# ads1115.net
KiCad netlist of a schematic drawn in EAGLE
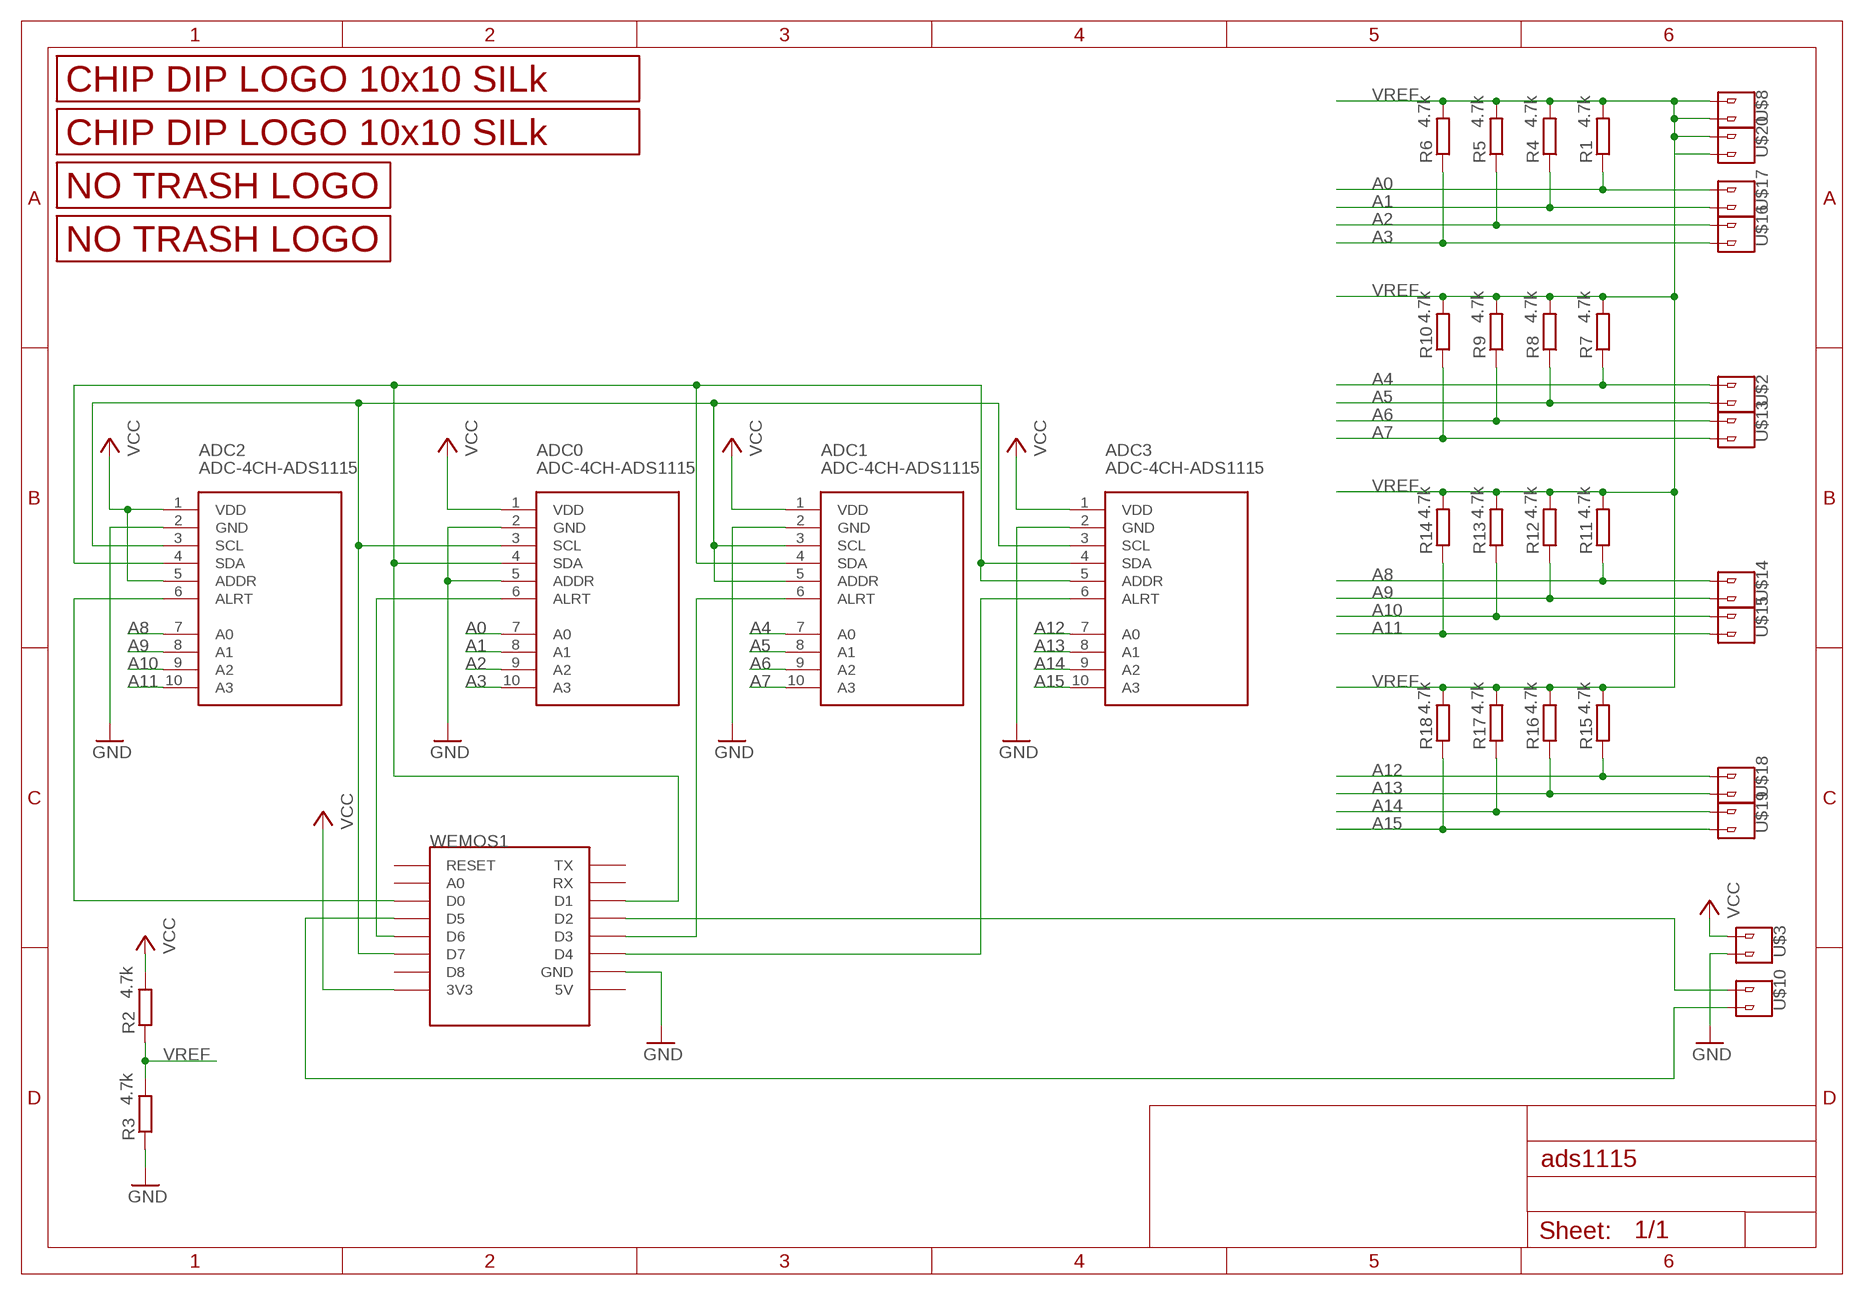
[diagram p0: schematic, sheet 1]

(export (version "E")
  (design (tool "Eeschema 10.0.6"))
  (components
    (comp (ref "ADC0")
      (value "ADC-4CH-ADS1115")
      (footprint "eagle-import:ADC-4CH-ADS1115_NO")
      (libsource (lib "eagle-import") (part "ADC-4CH-ADS1115"))
    )
    (comp (ref "ADC1")
      (value "ADC-4CH-ADS1115")
      (footprint "eagle-import:ADC-4CH-ADS1115_NO")
      (libsource (lib "eagle-import") (part "ADC-4CH-ADS1115"))
    )
    (comp (ref "ADC2")
      (value "ADC-4CH-ADS1115")
      (footprint "eagle-import:ADC-4CH-ADS1115_NO")
      (libsource (lib "eagle-import") (part "ADC-4CH-ADS1115"))
    )
    (comp (ref "ADC3")
      (value "ADC-4CH-ADS1115")
      (footprint "eagle-import:ADC-4CH-ADS1115_NO")
      (libsource (lib "eagle-import") (part "ADC-4CH-ADS1115"))
    )
    (comp (ref "R1")
      (value "4.7k")
      (footprint "eagle-import:M0805")
      (libsource (lib "eagle-import") (part "R-EU_M0805"))
    )
    (comp (ref "R2")
      (value "4.7k")
      (footprint "eagle-import:M0805")
      (libsource (lib "eagle-import") (part "R-EU_M0805"))
    )
    (comp (ref "R3")
      (value "4.7k")
      (footprint "eagle-import:M0805")
      (libsource (lib "eagle-import") (part "R-EU_M0805"))
    )
    (comp (ref "R4")
      (value "4.7k")
      (footprint "eagle-import:M0805")
      (libsource (lib "eagle-import") (part "R-EU_M0805"))
    )
    (comp (ref "R5")
      (value "4.7k")
      (footprint "eagle-import:M0805")
      (libsource (lib "eagle-import") (part "R-EU_M0805"))
    )
    (comp (ref "R6")
      (value "4.7k")
      (footprint "eagle-import:M0805")
      (libsource (lib "eagle-import") (part "R-EU_M0805"))
    )
    (comp (ref "R7")
      (value "4.7k")
      (footprint "eagle-import:M0805")
      (libsource (lib "eagle-import") (part "R-EU_M0805"))
    )
    (comp (ref "R8")
      (value "4.7k")
      (footprint "eagle-import:M0805")
      (libsource (lib "eagle-import") (part "R-EU_M0805"))
    )
    (comp (ref "R9")
      (value "4.7k")
      (footprint "eagle-import:M0805")
      (libsource (lib "eagle-import") (part "R-EU_M0805"))
    )
    (comp (ref "R10")
      (value "4.7k")
      (footprint "eagle-import:M0805")
      (libsource (lib "eagle-import") (part "R-EU_M0805"))
    )
    (comp (ref "R11")
      (value "4.7k")
      (footprint "eagle-import:M0805")
      (libsource (lib "eagle-import") (part "R-EU_M0805"))
    )
    (comp (ref "R12")
      (value "4.7k")
      (footprint "eagle-import:M0805")
      (libsource (lib "eagle-import") (part "R-EU_M0805"))
    )
    (comp (ref "R13")
      (value "4.7k")
      (footprint "eagle-import:M0805")
      (libsource (lib "eagle-import") (part "R-EU_M0805"))
    )
    (comp (ref "R14")
      (value "4.7k")
      (footprint "eagle-import:M0805")
      (libsource (lib "eagle-import") (part "R-EU_M0805"))
    )
    (comp (ref "R15")
      (value "4.7k")
      (footprint "eagle-import:M0805")
      (libsource (lib "eagle-import") (part "R-EU_M0805"))
    )
    (comp (ref "R16")
      (value "4.7k")
      (footprint "eagle-import:M0805")
      (libsource (lib "eagle-import") (part "R-EU_M0805"))
    )
    (comp (ref "R17")
      (value "4.7k")
      (footprint "eagle-import:M0805")
      (libsource (lib "eagle-import") (part "R-EU_M0805"))
    )
    (comp (ref "R18")
      (value "4.7k")
      (footprint "eagle-import:M0805")
      (libsource (lib "eagle-import") (part "R-EU_M0805"))
    )
    (comp (ref "U$1")
      (value "LOGO_10X10_SILK")
      (footprint "eagle-import:LOGO2_10X10_SILK")
      (libsource (lib "eagle-import") (part "LOGO_10X10_SILK"))
    )
    (comp (ref "U$2")
      (value "V1")
      (footprint "eagle-import:2_SCREW_PIN")
      (libsource (lib "eagle-import") (part "2_PIN_CONNECTOR"))
    )
    (comp (ref "U$3")
      (value "V1")
      (footprint "eagle-import:2_SCREW_PIN")
      (libsource (lib "eagle-import") (part "2_PIN_CONNECTOR"))
    )
    (comp (ref "U$4")
      (value "LOGO_NO_TRASHNO_TRASH")
      (footprint "eagle-import:LOGO_ROHS_NO_TRASH")
      (libsource (lib "eagle-import") (part "LOGO_NO_TRASHNO_TRASH"))
    )
    (comp (ref "U$8")
      (value "V1")
      (footprint "eagle-import:2_SCREW_PIN")
      (libsource (lib "eagle-import") (part "2_PIN_CONNECTOR"))
    )
    (comp (ref "U$9")
      (value "LOGO_NO_TRASHROHS")
      (footprint "eagle-import:LOGO_ROHS_SYM")
      (libsource (lib "eagle-import") (part "LOGO_NO_TRASHROHS"))
    )
    (comp (ref "U$10")
      (value "V1")
      (footprint "eagle-import:2_SCREW_PIN")
      (libsource (lib "eagle-import") (part "2_PIN_CONNECTOR"))
    )
    (comp (ref "U$11")
      (value "LOGO_10X10_SILK")
      (footprint "eagle-import:LOGO2_10X10_SILK")
      (libsource (lib "eagle-import") (part "LOGO_10X10_SILK"))
    )
    (comp (ref "U$13")
      (value "V1")
      (footprint "eagle-import:2_SCREW_PIN")
      (libsource (lib "eagle-import") (part "2_PIN_CONNECTOR"))
    )
    (comp (ref "U$14")
      (value "V1")
      (footprint "eagle-import:2_SCREW_PIN")
      (libsource (lib "eagle-import") (part "2_PIN_CONNECTOR"))
    )
    (comp (ref "U$15")
      (value "V1")
      (footprint "eagle-import:2_SCREW_PIN")
      (libsource (lib "eagle-import") (part "2_PIN_CONNECTOR"))
    )
    (comp (ref "U$16")
      (value "V1")
      (footprint "eagle-import:2_SCREW_PIN")
      (libsource (lib "eagle-import") (part "2_PIN_CONNECTOR"))
    )
    (comp (ref "U$17")
      (value "V1")
      (footprint "eagle-import:2_SCREW_PIN")
      (libsource (lib "eagle-import") (part "2_PIN_CONNECTOR"))
    )
    (comp (ref "U$18")
      (value "V1")
      (footprint "eagle-import:2_SCREW_PIN")
      (libsource (lib "eagle-import") (part "2_PIN_CONNECTOR"))
    )
    (comp (ref "U$19")
      (value "V1")
      (footprint "eagle-import:2_SCREW_PIN")
      (libsource (lib "eagle-import") (part "2_PIN_CONNECTOR"))
    )
    (comp (ref "U$20")
      (value "V1")
      (footprint "eagle-import:2_SCREW_PIN")
      (libsource (lib "eagle-import") (part "2_PIN_CONNECTOR"))
    )
    (comp (ref "WEMOS1")
      (value "WEMOS-D1-MINITXT")
      (footprint "eagle-import:WEMOS-D1-MINI")
      (libsource (lib "eagle-import") (part "WEMOS-D1-MINITXT"))
    )
  )
  (nets
    (net (code "1") (name "/A0") (class "Default")
      (node (ref "ADC0") (pin "7") (pinfunction "A0_7") (pintype "input"))
      (node (ref "R1") (pin "1") (pinfunction "1_1") (pintype "passive"))
      (node (ref "U$17") (pin "P$1") (pinfunction "1_P$1") (pintype "passive"))
    )
    (net (code "2") (name "/A1") (class "Default")
      (node (ref "ADC0") (pin "8") (pinfunction "A1_8") (pintype "input"))
      (node (ref "R4") (pin "1") (pinfunction "1_1") (pintype "passive"))
      (node (ref "U$17") (pin "P$2") (pinfunction "2_P$2") (pintype "passive"))
    )
    (net (code "3") (name "/A2") (class "Default")
      (node (ref "ADC0") (pin "9") (pinfunction "A2_9") (pintype "input"))
      (node (ref "R5") (pin "1") (pinfunction "1_1") (pintype "passive"))
      (node (ref "U$16") (pin "P$1") (pinfunction "1_P$1") (pintype "passive"))
    )
    (net (code "4") (name "/A3") (class "Default")
      (node (ref "ADC0") (pin "10") (pinfunction "A3_10") (pintype "input"))
      (node (ref "R6") (pin "1") (pinfunction "1_1") (pintype "passive"))
      (node (ref "U$16") (pin "P$2") (pinfunction "2_P$2") (pintype "passive"))
    )
    (net (code "5") (name "/A4") (class "Default")
      (node (ref "ADC1") (pin "7") (pinfunction "A0_7") (pintype "input"))
      (node (ref "R7") (pin "1") (pinfunction "1_1") (pintype "passive"))
      (node (ref "U$2") (pin "P$1") (pinfunction "1_P$1") (pintype "passive"))
    )
    (net (code "6") (name "/A5") (class "Default")
      (node (ref "ADC1") (pin "8") (pinfunction "A1_8") (pintype "input"))
      (node (ref "R8") (pin "1") (pinfunction "1_1") (pintype "passive"))
      (node (ref "U$2") (pin "P$2") (pinfunction "2_P$2") (pintype "passive"))
    )
    (net (code "7") (name "/A6") (class "Default")
      (node (ref "ADC1") (pin "9") (pinfunction "A2_9") (pintype "input"))
      (node (ref "R9") (pin "1") (pinfunction "1_1") (pintype "passive"))
      (node (ref "U$13") (pin "P$1") (pinfunction "1_P$1") (pintype "passive"))
    )
    (net (code "8") (name "/A7") (class "Default")
      (node (ref "ADC1") (pin "10") (pinfunction "A3_10") (pintype "input"))
      (node (ref "R10") (pin "1") (pinfunction "1_1") (pintype "passive"))
      (node (ref "U$13") (pin "P$2") (pinfunction "2_P$2") (pintype "passive"))
    )
    (net (code "9") (name "/A8") (class "Default")
      (node (ref "ADC2") (pin "7") (pinfunction "A0_7") (pintype "input"))
      (node (ref "R11") (pin "1") (pinfunction "1_1") (pintype "passive"))
      (node (ref "U$14") (pin "P$1") (pinfunction "1_P$1") (pintype "passive"))
    )
    (net (code "10") (name "/A9") (class "Default")
      (node (ref "ADC2") (pin "8") (pinfunction "A1_8") (pintype "input"))
      (node (ref "R12") (pin "1") (pinfunction "1_1") (pintype "passive"))
      (node (ref "U$14") (pin "P$2") (pinfunction "2_P$2") (pintype "passive"))
    )
    (net (code "11") (name "/A10") (class "Default")
      (node (ref "ADC2") (pin "9") (pinfunction "A2_9") (pintype "input"))
      (node (ref "R13") (pin "1") (pinfunction "1_1") (pintype "passive"))
      (node (ref "U$15") (pin "P$1") (pinfunction "1_P$1") (pintype "passive"))
    )
    (net (code "12") (name "/A11") (class "Default")
      (node (ref "ADC2") (pin "10") (pinfunction "A3_10") (pintype "input"))
      (node (ref "R14") (pin "1") (pinfunction "1_1") (pintype "passive"))
      (node (ref "U$15") (pin "P$2") (pinfunction "2_P$2") (pintype "passive"))
    )
    (net (code "13") (name "/A12") (class "Default")
      (node (ref "ADC3") (pin "7") (pinfunction "A0_7") (pintype "input"))
      (node (ref "R15") (pin "1") (pinfunction "1_1") (pintype "passive"))
      (node (ref "U$18") (pin "P$1") (pinfunction "1_P$1") (pintype "passive"))
    )
    (net (code "14") (name "/A13") (class "Default")
      (node (ref "ADC3") (pin "8") (pinfunction "A1_8") (pintype "input"))
      (node (ref "R16") (pin "1") (pinfunction "1_1") (pintype "passive"))
      (node (ref "U$18") (pin "P$2") (pinfunction "2_P$2") (pintype "passive"))
    )
    (net (code "15") (name "/A14") (class "Default")
      (node (ref "ADC3") (pin "9") (pinfunction "A2_9") (pintype "input"))
      (node (ref "R17") (pin "1") (pinfunction "1_1") (pintype "passive"))
      (node (ref "U$19") (pin "P$1") (pinfunction "1_P$1") (pintype "passive"))
    )
    (net (code "16") (name "/A15") (class "Default")
      (node (ref "ADC3") (pin "10") (pinfunction "A3_10") (pintype "input"))
      (node (ref "R18") (pin "1") (pinfunction "1_1") (pintype "passive"))
      (node (ref "U$19") (pin "P$2") (pinfunction "2_P$2") (pintype "passive"))
    )
    (net (code "17") (name "/VREF") (class "Default")
      (node (ref "R1") (pin "2") (pinfunction "2_2") (pintype "passive"))
      (node (ref "R10") (pin "2") (pinfunction "2_2") (pintype "passive"))
      (node (ref "R11") (pin "2") (pinfunction "2_2") (pintype "passive"))
      (node (ref "R12") (pin "2") (pinfunction "2_2") (pintype "passive"))
      (node (ref "R13") (pin "2") (pinfunction "2_2") (pintype "passive"))
      (node (ref "R14") (pin "2") (pinfunction "2_2") (pintype "passive"))
      (node (ref "R15") (pin "2") (pinfunction "2_2") (pintype "passive"))
      (node (ref "R16") (pin "2") (pinfunction "2_2") (pintype "passive"))
      (node (ref "R17") (pin "2") (pinfunction "2_2") (pintype "passive"))
      (node (ref "R18") (pin "2") (pinfunction "2_2") (pintype "passive"))
      (node (ref "R2") (pin "1") (pinfunction "1_1") (pintype "passive"))
      (node (ref "R3") (pin "2") (pinfunction "2_2") (pintype "passive"))
      (node (ref "R4") (pin "2") (pinfunction "2_2") (pintype "passive"))
      (node (ref "R5") (pin "2") (pinfunction "2_2") (pintype "passive"))
      (node (ref "R6") (pin "2") (pinfunction "2_2") (pintype "passive"))
      (node (ref "R7") (pin "2") (pinfunction "2_2") (pintype "passive"))
      (node (ref "R8") (pin "2") (pinfunction "2_2") (pintype "passive"))
      (node (ref "R9") (pin "2") (pinfunction "2_2") (pintype "passive"))
      (node (ref "U$20") (pin "P$1") (pinfunction "1_P$1") (pintype "passive"))
      (node (ref "U$20") (pin "P$2") (pinfunction "2_P$2") (pintype "passive"))
      (node (ref "U$8") (pin "P$1") (pinfunction "1_P$1") (pintype "passive"))
      (node (ref "U$8") (pin "P$2") (pinfunction "2_P$2") (pintype "passive"))
    )
    (net (code "18") (name "GND") (class "Default")
      (node (ref "ADC0") (pin "2") (pinfunction "GND_2") (pintype "power_in"))
      (node (ref "ADC0") (pin "5") (pinfunction "ADDR_5") (pintype "bidirectional"))
      (node (ref "ADC1") (pin "2") (pinfunction "GND_2") (pintype "power_in"))
      (node (ref "ADC2") (pin "2") (pinfunction "GND_2") (pintype "power_in"))
      (node (ref "ADC3") (pin "2") (pinfunction "GND_2") (pintype "power_in"))
      (node (ref "R3") (pin "1") (pinfunction "1_1") (pintype "passive"))
      (node (ref "U$3") (pin "P$2") (pinfunction "2_P$2") (pintype "passive"))
      (node (ref "WEMOS1") (pin "GND") (pinfunction "GND_GND") (pintype "bidirectional"))
    )
    (net (code "19") (name "Net-(ADC0-ALRT)") (class "Default")
      (node (ref "ADC0") (pin "6") (pinfunction "ALRT_6") (pintype "bidirectional"))
      (node (ref "WEMOS1") (pin "D6") (pinfunction "D6_D6") (pintype "bidirectional"))
    )
    (net (code "20") (name "Net-(ADC0-SCL)") (class "Default")
      (node (ref "ADC0") (pin "3") (pinfunction "SCL_3") (pintype "bidirectional"))
      (node (ref "ADC1") (pin "3") (pinfunction "SCL_3") (pintype "bidirectional"))
      (node (ref "ADC1") (pin "5") (pinfunction "ADDR_5") (pintype "bidirectional"))
      (node (ref "ADC2") (pin "3") (pinfunction "SCL_3") (pintype "bidirectional"))
      (node (ref "ADC3") (pin "3") (pinfunction "SCL_3") (pintype "bidirectional"))
      (node (ref "WEMOS1") (pin "D7") (pinfunction "D7_D7") (pintype "bidirectional"))
    )
    (net (code "21") (name "Net-(ADC0-SDA)") (class "Default")
      (node (ref "ADC0") (pin "4") (pinfunction "SDA_4") (pintype "bidirectional"))
      (node (ref "ADC1") (pin "4") (pinfunction "SDA_4") (pintype "bidirectional"))
      (node (ref "ADC2") (pin "4") (pinfunction "SDA_4") (pintype "bidirectional"))
      (node (ref "ADC3") (pin "4") (pinfunction "SDA_4") (pintype "bidirectional"))
      (node (ref "ADC3") (pin "5") (pinfunction "ADDR_5") (pintype "bidirectional"))
      (node (ref "WEMOS1") (pin "D1") (pinfunction "D1_D1") (pintype "bidirectional"))
    )
    (net (code "22") (name "Net-(ADC1-ALRT)") (class "Default")
      (node (ref "ADC1") (pin "6") (pinfunction "ALRT_6") (pintype "bidirectional"))
      (node (ref "WEMOS1") (pin "D3") (pinfunction "D3_D3") (pintype "bidirectional"))
    )
    (net (code "23") (name "Net-(ADC2-ALRT)") (class "Default")
      (node (ref "ADC2") (pin "6") (pinfunction "ALRT_6") (pintype "bidirectional"))
      (node (ref "WEMOS1") (pin "D0") (pinfunction "D0_D0") (pintype "bidirectional"))
    )
    (net (code "24") (name "Net-(ADC3-ALRT)") (class "Default")
      (node (ref "ADC3") (pin "6") (pinfunction "ALRT_6") (pintype "bidirectional"))
      (node (ref "WEMOS1") (pin "D4") (pinfunction "D4_D4") (pintype "bidirectional"))
    )
    (net (code "25") (name "Net-(U$10-1)") (class "Default")
      (node (ref "U$10") (pin "P$1") (pinfunction "1_P$1") (pintype "passive"))
      (node (ref "WEMOS1") (pin "D2") (pinfunction "D2_D2") (pintype "bidirectional"))
    )
    (net (code "26") (name "Net-(U$10-2)") (class "Default")
      (node (ref "U$10") (pin "P$2") (pinfunction "2_P$2") (pintype "passive"))
      (node (ref "WEMOS1") (pin "D5") (pinfunction "D5_D5") (pintype "bidirectional"))
    )
    (net (code "27") (name "VCC") (class "Default")
      (node (ref "ADC0") (pin "1") (pinfunction "VDD_1") (pintype "power_in"))
      (node (ref "ADC1") (pin "1") (pinfunction "VDD_1") (pintype "power_in"))
      (node (ref "ADC2") (pin "1") (pinfunction "VDD_1") (pintype "power_in"))
      (node (ref "ADC2") (pin "5") (pinfunction "ADDR_5") (pintype "bidirectional"))
      (node (ref "ADC3") (pin "1") (pinfunction "VDD_1") (pintype "power_in"))
      (node (ref "R2") (pin "2") (pinfunction "2_2") (pintype "passive"))
      (node (ref "U$3") (pin "P$1") (pinfunction "1_P$1") (pintype "passive"))
      (node (ref "WEMOS1") (pin "3V3") (pinfunction "3V3_3V3") (pintype "bidirectional"))
    )
    (net (code "28") (name "unconnected-(WEMOS1-Pad5V)") (class "Default")
      (node (ref "WEMOS1") (pin "5V") (pinfunction "5V_5V") (pintype "bidirectional"))
    )
    (net (code "29") (name "unconnected-(WEMOS1-PadA0)") (class "Default")
      (node (ref "WEMOS1") (pin "A0") (pinfunction "A0_A0") (pintype "bidirectional"))
    )
    (net (code "30") (name "unconnected-(WEMOS1-PadD8)") (class "Default")
      (node (ref "WEMOS1") (pin "D8") (pinfunction "D8_D8") (pintype "bidirectional"))
    )
    (net (code "31") (name "unconnected-(WEMOS1-PadRESET)") (class "Default")
      (node (ref "WEMOS1") (pin "RESET") (pinfunction "RESET_RESET") (pintype "bidirectional"))
    )
    (net (code "32") (name "unconnected-(WEMOS1-PadRX)") (class "Default")
      (node (ref "WEMOS1") (pin "RX") (pinfunction "RX_RX") (pintype "bidirectional"))
    )
    (net (code "33") (name "unconnected-(WEMOS1-PadTX)") (class "Default")
      (node (ref "WEMOS1") (pin "TX") (pinfunction "TX_TX") (pintype "bidirectional"))
    )
  )
)
